# RADM-Power-S02-V00.net
KiCad netlist of a schematic drawn in Altium Designer
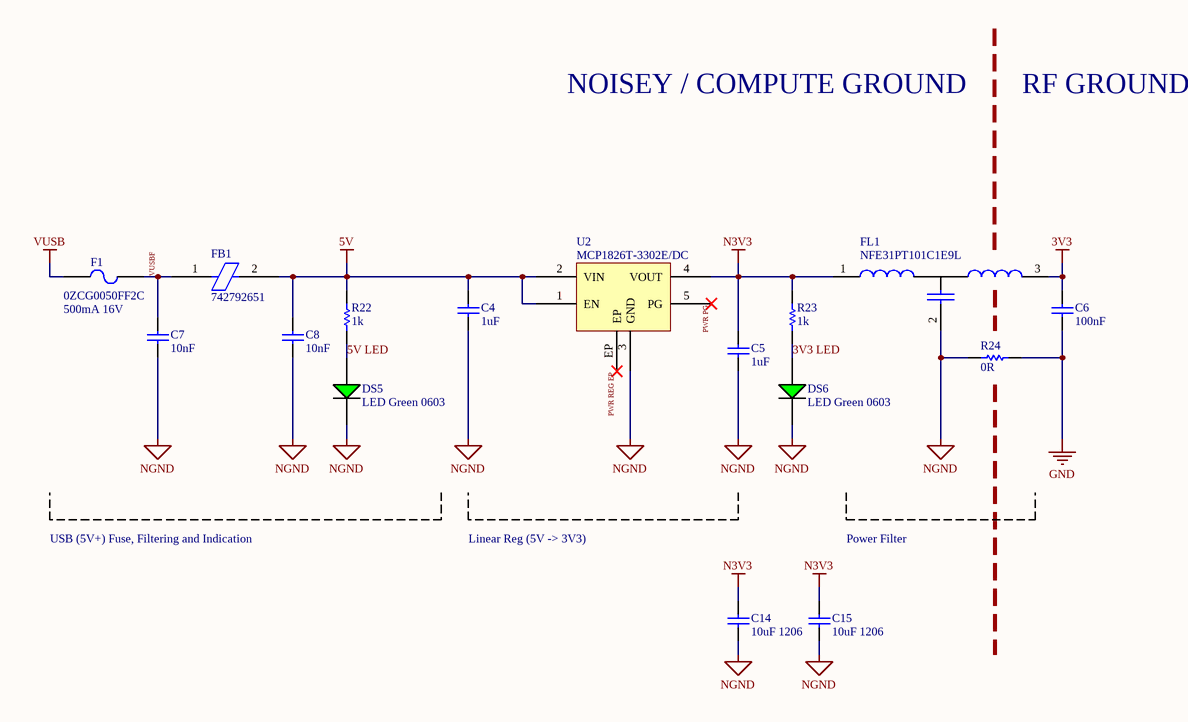
[diagram p0: RADM-Power-S02-V00.SchDoc]

(export (version "E")
  (design (tool "Eeschema 10.0.6"))
  (components
    (comp (ref "C4")
      (value "1uF")
      (footprint "Cap_Ceramic_0603")
      (description "Capacitor, Ceramic, SMD, 1uF, 25V, 5%, X7R, 0603")
      (libsource (lib "StandardCapacitors") (part "1uF 25V 5% X7R 0603"))
    )
    (comp (ref "C5")
      (value "1uF")
      (footprint "Cap_Ceramic_0603")
      (description "Capacitor, Ceramic, SMD, 1uF, 25V, 5%, X7R, 0603")
      (libsource (lib "StandardCapacitors") (part "1uF 25V 5% X7R 0603"))
    )
    (comp (ref "C6")
      (value "100nF")
      (footprint "Cap_Ceramic_0603")
      (description "Capacitor, Ceramic, SMD, 100nF, 50V, 5%, X7R, 0603")
      (libsource (lib "StandardCapacitors") (part "100nF 50V 5% X7R 0603"))
    )
    (comp (ref "C7")
      (value "10nF")
      (footprint "Cap_Ceramic_0603")
      (description "Capacitor, Ceramic, SMD, 10nF, 50V, 5%, X7R, 0603")
      (libsource (lib "StandardCapacitors") (part "10nF 50V 5% X7R 0603"))
    )
    (comp (ref "C8")
      (value "10nF")
      (footprint "Cap_Ceramic_0603")
      (description "Capacitor, Ceramic, SMD, 10nF, 50V, 5%, X7R, 0603")
      (libsource (lib "StandardCapacitors") (part "10nF 50V 5% X7R 0603"))
    )
    (comp (ref "C14")
      (value "10uF 1206")
      (footprint "Cap_Ceramic_1206")
      (description "Capacitor, Ceramic, SMD, 10uF, 25V, 10%, X7R, 1206")
      (libsource (lib "StandardCapacitors") (part "10uF 25V 10% X7R 1206"))
    )
    (comp (ref "C15")
      (value "10uF 1206")
      (footprint "Cap_Ceramic_1206")
      (description "Capacitor, Ceramic, SMD, 10uF, 25V, 10%, X7R, 1206")
      (libsource (lib "StandardCapacitors") (part "10uF 25V 10% X7R 1206"))
    )
    (comp (ref "DS5")
      (value "LED Green 0603")
      (footprint "LED GREEN 0603")
      (libsource (lib "QUTMS_LEDLibrary") (part "LED Green 0603"))
    )
    (comp (ref "DS6")
      (value "LED Green 0603")
      (footprint "LED GREEN 0603")
      (libsource (lib "QUTMS_LEDLibrary") (part "LED Green 0603"))
    )
    (comp (ref "F1")
      (value "0ZCG0050FF2C")
      (footprint "1812 FUSE")
      (description "Polymeric PTC Resettable Fuse 16V 500mA Ih Surface Mount 1812 (4532 Metric), Concave")
      (libsource (lib "QUTMS_FuseLibrary") (part "0ZCG0050FF2C"))
    )
    (comp (ref "FB1")
      (value "742792651")
      (footprint "Inductor_0603")
      (description "600 Ohms @ 100MHz 1 Signal Line Ferrite Bead 0603 (1608 Metric) 1A 200mOhm")
      (libsource (lib "QUTMS_InductorLibrary") (part "742792651"))
    )
    (comp (ref "FL1")
      (value "NFE31PT101C1E9L")
      (footprint "NFE31PT101C1E9L")
      (description "LC (T-Type) EMI Filter 3rd Order Low Pass 1 Channel C = 100pF 6A 1206 (3216 Metric), 3 PC Pad")
      (libsource (lib "QUTMS_PowerSupplyLibrary") (part "NFE31PT101C1E9L"))
    )
    (comp (ref "R22")
      (value "1k")
      (footprint "Res_ThinFilm_0603")
      (description "Resistor, SMD, 1k, 0.1W, 5%, 0603")
      (libsource (lib "StandardResistors") (part "1k 5% 0603"))
    )
    (comp (ref "R23")
      (value "1k")
      (footprint "Res_ThinFilm_0603")
      (description "Resistor, SMD, 1k, 0.1W, 5%, 0603")
      (libsource (lib "StandardResistors") (part "1k 5% 0603"))
    )
    (comp (ref "R24")
      (value "0R")
      (footprint "Res_ThinFilm_0603")
      (description "Resistor, SMD, 0R, 0.1W, 5%, 0603")
      (libsource (lib "StandardResistors") (part "0R 5% 0603"))
    )
    (comp (ref "U2")
      (value "MCP1826T-3302E/DC")
      (footprint "SOT-223-5")
      (description "Linear Voltage Regulator IC Positive Fixed 1 Output 1A SOT-223-5")
      (libsource (lib "QUTMS_PowerSupplyLibrary") (part "MCP1826T-3302E/DC"))
    )
  )
  (nets
    (net (code "1") (name "/3V3 LED") (class "Default")
      (node (ref "DS6") (pin "1") (pinfunction "A_1") (pintype "passive"))
      (node (ref "R23") (pin "1") (pinfunction "1_1") (pintype "passive"))
    )
    (net (code "2") (name "/5V LED") (class "Default")
      (node (ref "DS5") (pin "1") (pinfunction "A_1") (pintype "passive"))
      (node (ref "R22") (pin "1") (pinfunction "1_1") (pintype "passive"))
    )
    (net (code "3") (name "/PWR PG") (class "Default")
      (node (ref "U2") (pin "5") (pinfunction "PG_5") (pintype "passive+no_connect"))
    )
    (net (code "4") (name "/PWR REG EP") (class "Default")
      (node (ref "U2") (pin "EP") (pinfunction "EP_EP") (pintype "passive+no_connect"))
    )
    (net (code "5") (name "/VUSBF") (class "Default")
      (node (ref "C7") (pin "2") (pinfunction "2_2") (pintype "passive"))
      (node (ref "F1") (pin "2") (pinfunction "2_2") (pintype "passive"))
      (node (ref "FB1") (pin "1") (pinfunction "1_1") (pintype "passive"))
    )
    (net (code "6") (name "3V3") (class "Default")
      (node (ref "C6") (pin "2") (pinfunction "2_2") (pintype "passive"))
      (node (ref "FL1") (pin "3") (pinfunction "3_3") (pintype "passive"))
    )
    (net (code "7") (name "5V") (class "Default")
      (node (ref "C4") (pin "2") (pinfunction "2_2") (pintype "passive"))
      (node (ref "C8") (pin "2") (pinfunction "2_2") (pintype "passive"))
      (node (ref "FB1") (pin "2") (pinfunction "2_2") (pintype "passive"))
      (node (ref "R22") (pin "2") (pinfunction "2_2") (pintype "passive"))
      (node (ref "U2") (pin "1") (pinfunction "EN_1") (pintype "passive"))
      (node (ref "U2") (pin "2") (pinfunction "VIN_2") (pintype "passive"))
    )
    (net (code "8") (name "GND") (class "Default")
      (node (ref "C6") (pin "1") (pinfunction "1_1") (pintype "passive"))
      (node (ref "R24") (pin "2") (pinfunction "2_2") (pintype "passive"))
    )
    (net (code "9") (name "N3V3") (class "Default")
      (node (ref "C14") (pin "2") (pinfunction "2_2") (pintype "passive"))
      (node (ref "C15") (pin "2") (pinfunction "2_2") (pintype "passive"))
      (node (ref "C5") (pin "2") (pinfunction "2_2") (pintype "passive"))
      (node (ref "FL1") (pin "1") (pinfunction "1_1") (pintype "passive"))
      (node (ref "R23") (pin "2") (pinfunction "2_2") (pintype "passive"))
      (node (ref "U2") (pin "4") (pinfunction "VOUT_4") (pintype "passive"))
    )
    (net (code "10") (name "NGND") (class "Default")
      (node (ref "C14") (pin "1") (pinfunction "1_1") (pintype "passive"))
      (node (ref "C15") (pin "1") (pinfunction "1_1") (pintype "passive"))
      (node (ref "C4") (pin "1") (pinfunction "1_1") (pintype "passive"))
      (node (ref "C5") (pin "1") (pinfunction "1_1") (pintype "passive"))
      (node (ref "C7") (pin "1") (pinfunction "1_1") (pintype "passive"))
      (node (ref "C8") (pin "1") (pinfunction "1_1") (pintype "passive"))
      (node (ref "DS5") (pin "2") (pinfunction "C_2") (pintype "passive"))
      (node (ref "DS6") (pin "2") (pinfunction "C_2") (pintype "passive"))
      (node (ref "FL1") (pin "2") (pinfunction "2_2") (pintype "passive"))
      (node (ref "R24") (pin "1") (pinfunction "1_1") (pintype "passive"))
      (node (ref "U2") (pin "3") (pinfunction "GND_3") (pintype "passive"))
    )
    (net (code "11") (name "VUSB") (class "Default")
      (node (ref "F1") (pin "1") (pinfunction "1_1") (pintype "passive"))
    )
  )
)
